# Hatch2020Trophy0805_1.net
KiCad netlist of a schematic drawn in EAGLE
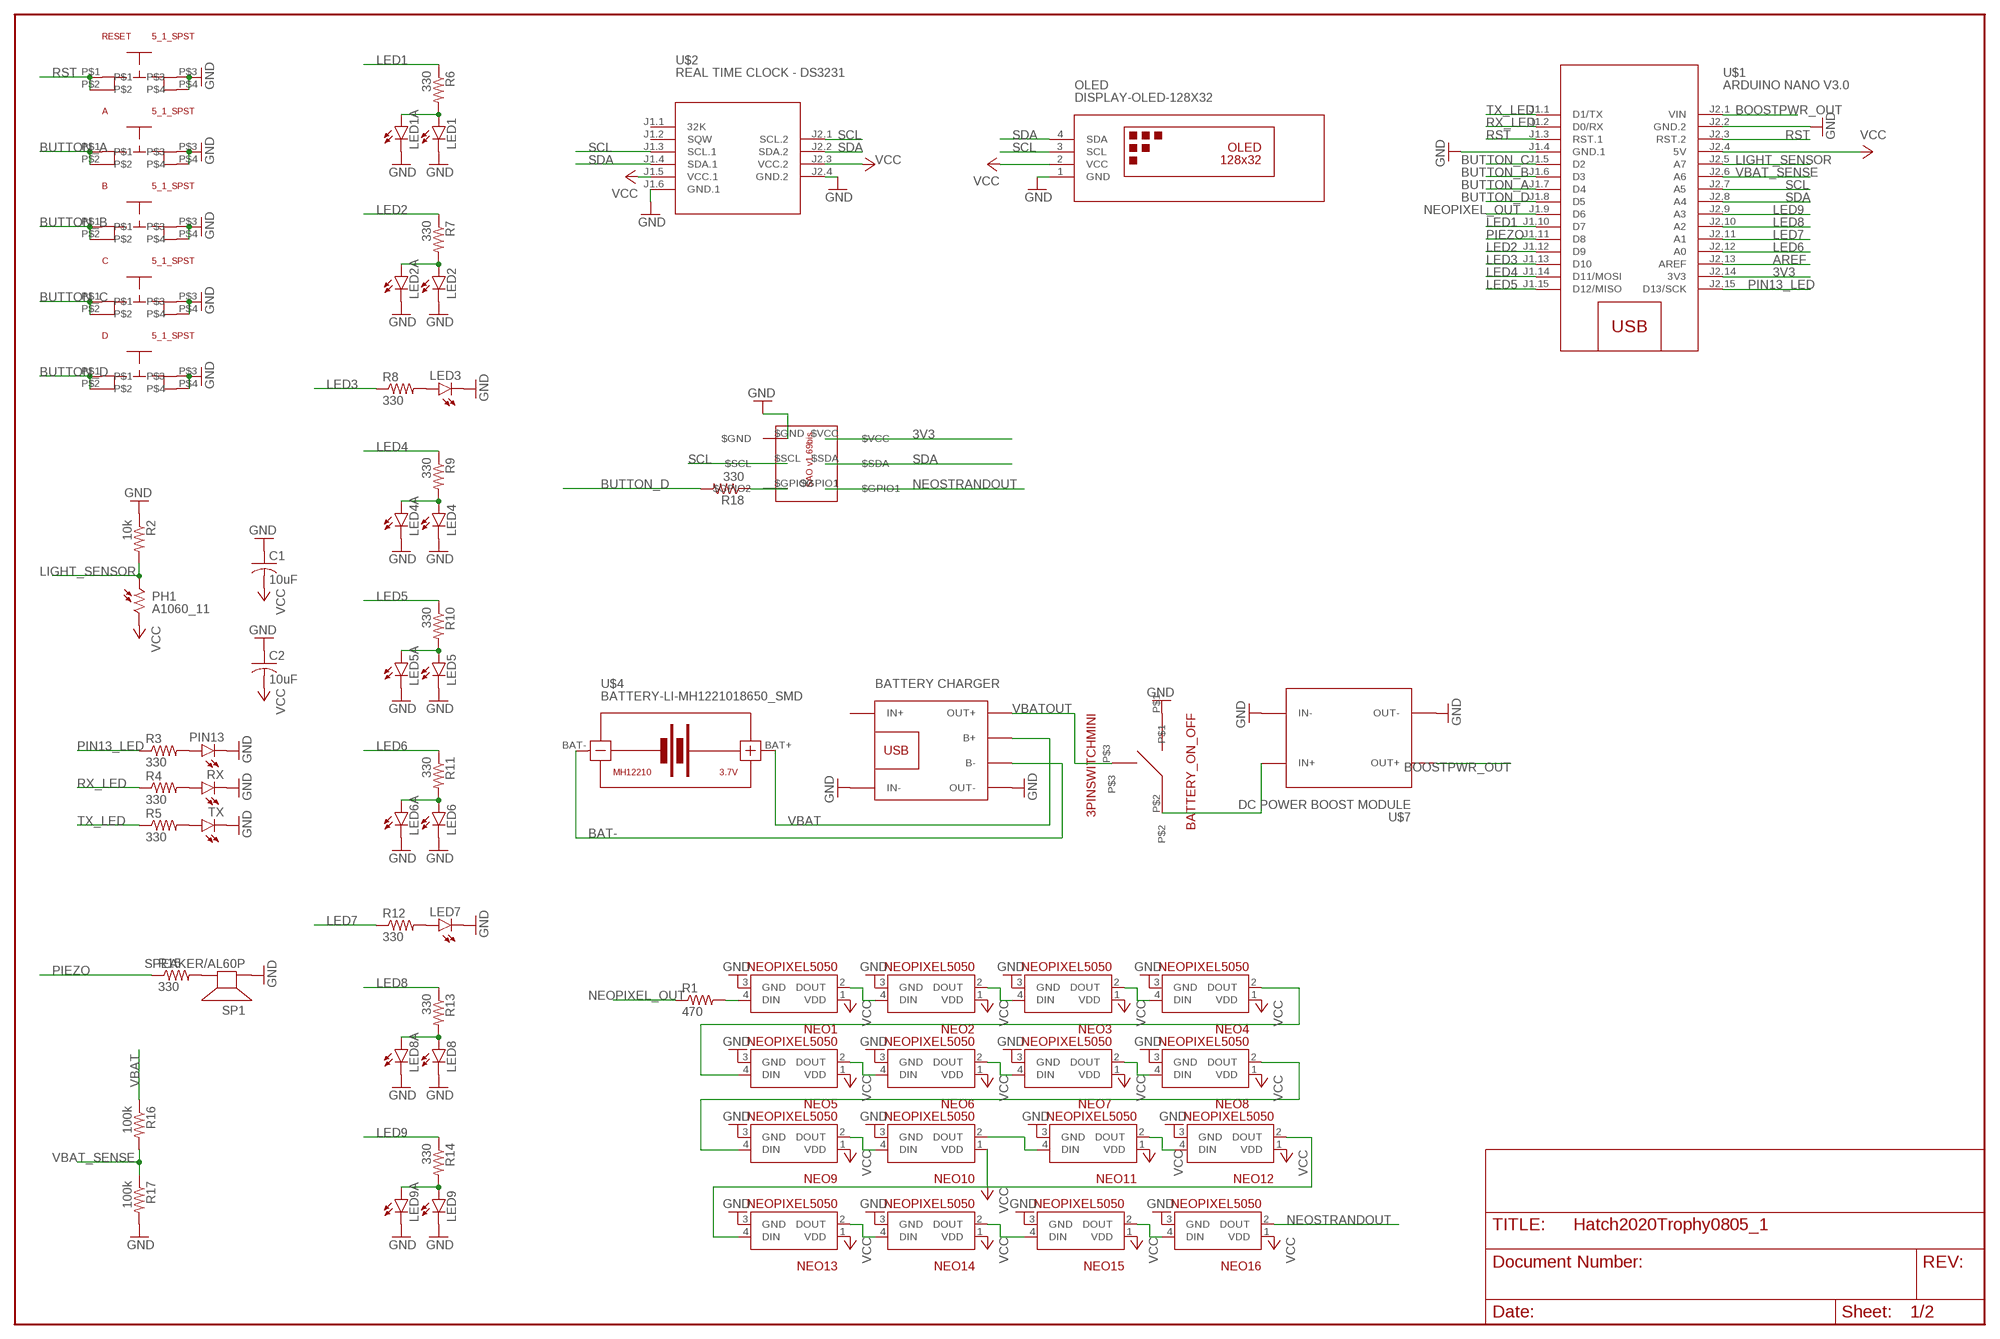
[diagram p0: schematic, sheet 1]

(export (version "E")
  (design (tool "Eeschema 10.0.6"))
  (components
    (comp (ref "A")
      (value "5_1_SPST")
      (footprint "eagle-import:5_1_SPST")
      (libsource (lib "eagle-import") (part "5_1_SPST"))
    )
    (comp (ref "B")
      (value "5_1_SPST")
      (footprint "eagle-import:5_1_SPST")
      (libsource (lib "eagle-import") (part "5_1_SPST"))
    )
    (comp (ref "BATTERY_ON_OFF")
      (value "3PINSWITCHMINI")
      (footprint "eagle-import:3PINMINI")
      (libsource (lib "eagle-import") (part "3PINSWITCHMINI"))
    )
    (comp (ref "C")
      (value "5_1_SPST")
      (footprint "eagle-import:5_1_SPST")
      (libsource (lib "eagle-import") (part "5_1_SPST"))
    )
    (comp (ref "C1")
      (value "10uF")
      (footprint "eagle-import:C0805")
      (libsource (lib "eagle-import") (part "C-USC0805"))
    )
    (comp (ref "C2")
      (value "10uF")
      (footprint "eagle-import:C0805")
      (libsource (lib "eagle-import") (part "C-USC0805"))
    )
    (comp (ref "D")
      (value "5_1_SPST")
      (footprint "eagle-import:5_1_SPST")
      (libsource (lib "eagle-import") (part "5_1_SPST"))
    )
    (comp (ref "LED1")
      (value "LEDSML0805")
      (footprint "eagle-import:SML0805")
      (libsource (lib "eagle-import") (part "LEDSML0805"))
    )
    (comp (ref "LED1A")
      (value "LEDSML0805")
      (footprint "eagle-import:SML0805")
      (libsource (lib "eagle-import") (part "LEDSML0805"))
    )
    (comp (ref "LED2")
      (value "LEDSML0805")
      (footprint "eagle-import:SML0805")
      (libsource (lib "eagle-import") (part "LEDSML0805"))
    )
    (comp (ref "LED2A")
      (value "LEDSML0805")
      (footprint "eagle-import:SML0805")
      (libsource (lib "eagle-import") (part "LEDSML0805"))
    )
    (comp (ref "LED3")
      (value "LEDSML0805")
      (footprint "eagle-import:SML0805")
      (libsource (lib "eagle-import") (part "LEDSML0805"))
    )
    (comp (ref "LED4")
      (value "LEDSML0805")
      (footprint "eagle-import:SML0805")
      (libsource (lib "eagle-import") (part "LEDSML0805"))
    )
    (comp (ref "LED4A")
      (value "LEDSML0805")
      (footprint "eagle-import:SML0805")
      (libsource (lib "eagle-import") (part "LEDSML0805"))
    )
    (comp (ref "LED5")
      (value "LEDSML0805")
      (footprint "eagle-import:SML0805")
      (libsource (lib "eagle-import") (part "LEDSML0805"))
    )
    (comp (ref "LED5A")
      (value "LEDSML0805")
      (footprint "eagle-import:SML0805")
      (libsource (lib "eagle-import") (part "LEDSML0805"))
    )
    (comp (ref "LED6")
      (value "LEDSML0805")
      (footprint "eagle-import:SML0805")
      (libsource (lib "eagle-import") (part "LEDSML0805"))
    )
    (comp (ref "LED6A")
      (value "LEDSML0805")
      (footprint "eagle-import:SML0805")
      (libsource (lib "eagle-import") (part "LEDSML0805"))
    )
    (comp (ref "LED7")
      (value "LEDSML0805")
      (footprint "eagle-import:SML0805")
      (libsource (lib "eagle-import") (part "LEDSML0805"))
    )
    (comp (ref "LED8")
      (value "LEDSML0805")
      (footprint "eagle-import:SML0805")
      (libsource (lib "eagle-import") (part "LEDSML0805"))
    )
    (comp (ref "LED8A")
      (value "LEDSML0805")
      (footprint "eagle-import:SML0805")
      (libsource (lib "eagle-import") (part "LEDSML0805"))
    )
    (comp (ref "LED9")
      (value "LEDSML0805")
      (footprint "eagle-import:SML0805")
      (libsource (lib "eagle-import") (part "LEDSML0805"))
    )
    (comp (ref "LED9A")
      (value "LEDSML0805")
      (footprint "eagle-import:SML0805")
      (libsource (lib "eagle-import") (part "LEDSML0805"))
    )
    (comp (ref "NEO1")
      (value "NEOPIXEL5050")
      (footprint "eagle-import:NEOPIXEL5050")
      (libsource (lib "eagle-import") (part "NEOPIXEL5050"))
    )
    (comp (ref "NEO2")
      (value "NEOPIXEL5050")
      (footprint "eagle-import:NEOPIXEL5050")
      (libsource (lib "eagle-import") (part "NEOPIXEL5050"))
    )
    (comp (ref "NEO3")
      (value "NEOPIXEL5050")
      (footprint "eagle-import:NEOPIXEL5050")
      (libsource (lib "eagle-import") (part "NEOPIXEL5050"))
    )
    (comp (ref "NEO4")
      (value "NEOPIXEL5050")
      (footprint "eagle-import:NEOPIXEL5050")
      (libsource (lib "eagle-import") (part "NEOPIXEL5050"))
    )
    (comp (ref "NEO5")
      (value "NEOPIXEL5050")
      (footprint "eagle-import:NEOPIXEL5050")
      (libsource (lib "eagle-import") (part "NEOPIXEL5050"))
    )
    (comp (ref "NEO6")
      (value "NEOPIXEL5050")
      (footprint "eagle-import:NEOPIXEL5050")
      (libsource (lib "eagle-import") (part "NEOPIXEL5050"))
    )
    (comp (ref "NEO7")
      (value "NEOPIXEL5050")
      (footprint "eagle-import:NEOPIXEL5050")
      (libsource (lib "eagle-import") (part "NEOPIXEL5050"))
    )
    (comp (ref "NEO8")
      (value "NEOPIXEL5050")
      (footprint "eagle-import:NEOPIXEL5050")
      (libsource (lib "eagle-import") (part "NEOPIXEL5050"))
    )
    (comp (ref "NEO9")
      (value "NEOPIXEL5050")
      (footprint "eagle-import:NEOPIXEL5050")
      (libsource (lib "eagle-import") (part "NEOPIXEL5050"))
    )
    (comp (ref "NEO10")
      (value "NEOPIXEL5050")
      (footprint "eagle-import:NEOPIXEL5050")
      (libsource (lib "eagle-import") (part "NEOPIXEL5050"))
    )
    (comp (ref "NEO11")
      (value "NEOPIXEL5050")
      (footprint "eagle-import:NEOPIXEL5050")
      (libsource (lib "eagle-import") (part "NEOPIXEL5050"))
    )
    (comp (ref "NEO12")
      (value "NEOPIXEL5050")
      (footprint "eagle-import:NEOPIXEL5050")
      (libsource (lib "eagle-import") (part "NEOPIXEL5050"))
    )
    (comp (ref "NEO13")
      (value "NEOPIXEL5050")
      (footprint "eagle-import:NEOPIXEL5050")
      (libsource (lib "eagle-import") (part "NEOPIXEL5050"))
    )
    (comp (ref "NEO14")
      (value "NEOPIXEL5050")
      (footprint "eagle-import:NEOPIXEL5050")
      (libsource (lib "eagle-import") (part "NEOPIXEL5050"))
    )
    (comp (ref "NEO15")
      (value "NEOPIXEL5050")
      (footprint "eagle-import:NEOPIXEL5050")
      (libsource (lib "eagle-import") (part "NEOPIXEL5050"))
    )
    (comp (ref "NEO16")
      (value "NEOPIXEL5050")
      (footprint "eagle-import:NEOPIXEL5050")
      (libsource (lib "eagle-import") (part "NEOPIXEL5050"))
    )
    (comp (ref "OLED")
      (value "DISPLAY-OLED-128X32")
      (footprint "eagle-import:DISPLAY-OLED-128X32")
      (libsource (lib "eagle-import") (part "DISPLAY-OLED-128X32"))
    )
    (comp (ref "PH1")
      (value "A1060_11")
      (footprint "eagle-import:T0-46-A10XX")
      (libsource (lib "eagle-import") (part "A1060_11"))
    )
    (comp (ref "PIN13")
      (value "LEDSML0805")
      (footprint "eagle-import:SML0805")
      (libsource (lib "eagle-import") (part "LEDSML0805"))
    )
    (comp (ref "R1")
      (value "470")
      (footprint "eagle-import:R0805")
      (libsource (lib "eagle-import") (part "R-US_R0805"))
    )
    (comp (ref "R2")
      (value "10k")
      (footprint "eagle-import:R0805")
      (libsource (lib "eagle-import") (part "R-US_R0805"))
    )
    (comp (ref "R3")
      (value "330")
      (footprint "eagle-import:R0805")
      (libsource (lib "eagle-import") (part "R-US_R0805"))
    )
    (comp (ref "R4")
      (value "330")
      (footprint "eagle-import:R0805")
      (libsource (lib "eagle-import") (part "R-US_R0805"))
    )
    (comp (ref "R5")
      (value "330")
      (footprint "eagle-import:R0805")
      (libsource (lib "eagle-import") (part "R-US_R0805"))
    )
    (comp (ref "R6")
      (value "330")
      (footprint "eagle-import:R0805")
      (libsource (lib "eagle-import") (part "R-US_R0805"))
    )
    (comp (ref "R7")
      (value "330")
      (footprint "eagle-import:R0805")
      (libsource (lib "eagle-import") (part "R-US_R0805"))
    )
    (comp (ref "R8")
      (value "330")
      (footprint "eagle-import:R0805")
      (libsource (lib "eagle-import") (part "R-US_R0805"))
    )
    (comp (ref "R9")
      (value "330")
      (footprint "eagle-import:R0805")
      (libsource (lib "eagle-import") (part "R-US_R0805"))
    )
    (comp (ref "R10")
      (value "330")
      (footprint "eagle-import:R0805")
      (libsource (lib "eagle-import") (part "R-US_R0805"))
    )
    (comp (ref "R11")
      (value "330")
      (footprint "eagle-import:R0805")
      (libsource (lib "eagle-import") (part "R-US_R0805"))
    )
    (comp (ref "R12")
      (value "330")
      (footprint "eagle-import:R0805")
      (libsource (lib "eagle-import") (part "R-US_R0805"))
    )
    (comp (ref "R13")
      (value "330")
      (footprint "eagle-import:R0805")
      (libsource (lib "eagle-import") (part "R-US_R0805"))
    )
    (comp (ref "R14")
      (value "330")
      (footprint "eagle-import:R0805")
      (libsource (lib "eagle-import") (part "R-US_R0805"))
    )
    (comp (ref "R15")
      (value "330")
      (footprint "eagle-import:R0805")
      (libsource (lib "eagle-import") (part "R-US_R0805"))
    )
    (comp (ref "R16")
      (value "100k")
      (footprint "eagle-import:R0805")
      (libsource (lib "eagle-import") (part "R-US_R0805"))
    )
    (comp (ref "R17")
      (value "100k")
      (footprint "eagle-import:R0805")
      (libsource (lib "eagle-import") (part "R-US_R0805"))
    )
    (comp (ref "R18")
      (value "330")
      (footprint "eagle-import:R1206")
      (libsource (lib "eagle-import") (part "R-US_R1206"))
    )
    (comp (ref "RESET")
      (value "5_1_SPST")
      (footprint "eagle-import:5_1_SPST")
      (libsource (lib "eagle-import") (part "5_1_SPST"))
    )
    (comp (ref "RX")
      (value "LEDSML0805")
      (footprint "eagle-import:SML0805")
      (libsource (lib "eagle-import") (part "LEDSML0805"))
    )
    (comp (ref "SP1")
      (value "SPEAKER/AL60P")
      (footprint "eagle-import:AL60P")
      (libsource (lib "eagle-import") (part "SPEAKER/AL60P"))
    )
    (comp (ref "TX")
      (value "LEDSML0805")
      (footprint "eagle-import:SML0805")
      (libsource (lib "eagle-import") (part "LEDSML0805"))
    )
    (comp (ref "U$1")
      (value "ARDUINO NANO V3.0")
      (footprint "eagle-import:ARDUINO-NANO-3.0")
      (libsource (lib "eagle-import") (part "ARDUINO-NANO-3.0"))
    )
    (comp (ref "U$2")
      (value "REAL TIME CLOCK - DS3231")
      (footprint "eagle-import:RTC-DS3231-AT24C32")
      (libsource (lib "eagle-import") (part "RTC-DS3231-AT24C32"))
    )
    (comp (ref "U$3")
      (value "SAO-1.69")
      (footprint "eagle-import:2X3-SHROUDED-FEMALE")
      (libsource (lib "eagle-import") (part "SAO-1.69"))
    )
    (comp (ref "U$4")
      (value "BATTERY-LI-MH1221018650_SMD")
      (footprint "eagle-import:BATTERY_18650_SMD")
      (libsource (lib "eagle-import") (part "BATTERY-LI-MH1221018650_SMD"))
    )
    (comp (ref "U$6")
      (value "BATTERY CHARGER")
      (footprint "eagle-import:BAT_CHARGE_LOW_FP")
      (libsource (lib "eagle-import") (part "BATTERY-CHARGER-LI-PROTLOW_FP"))
    )
    (comp (ref "U$7")
      (value "DC POWER BOOST MODULE")
      (footprint "eagle-import:DC-DC-STEP-UP-LOW_FP")
      (libsource (lib "eagle-import") (part "DC-DC-STEP-UP-MT3608LOW_FP"))
    )
  )
  (nets
    (net (code "1") (name "3V3") (class "Default")
      (node (ref "U$1") (pin "J2.14") (pinfunction "3V3_J2.14") (pintype "power_in"))
      (node (ref "U$3") (pin "$VCC") (pinfunction "$VCC_$VCC") (pintype "bidirectional"))
    )
    (net (code "2") (name "AREF") (class "Default")
      (node (ref "U$1") (pin "J2.13") (pinfunction "AREF_J2.13") (pintype "bidirectional"))
    )
    (net (code "3") (name "BAT-") (class "Default")
      (node (ref "U$4") (pin "BAT-") (pinfunction "BAT-_BAT-") (pintype "power_in"))
      (node (ref "U$6") (pin "B-") (pinfunction "B-_B-") (pintype "bidirectional"))
    )
    (net (code "4") (name "BOOSTPWR_OUT") (class "Default")
      (node (ref "U$1") (pin "J2.1") (pinfunction "VIN_J2.1") (pintype "power_in"))
      (node (ref "U$7") (pin "OUT+") (pinfunction "OUT+_OUT+") (pintype "bidirectional"))
    )
    (net (code "5") (name "BUTTON_A") (class "Default")
      (node (ref "A") (pin "P$1") (pinfunction "P$1_P$1") (pintype "bidirectional"))
      (node (ref "A") (pin "P$2") (pinfunction "P$2_P$2") (pintype "bidirectional"))
      (node (ref "U$1") (pin "J1.7") (pinfunction "D4_J1.7") (pintype "bidirectional"))
    )
    (net (code "6") (name "BUTTON_B") (class "Default")
      (node (ref "B") (pin "P$1") (pinfunction "P$1_P$1") (pintype "bidirectional"))
      (node (ref "B") (pin "P$2") (pinfunction "P$2_P$2") (pintype "bidirectional"))
      (node (ref "U$1") (pin "J1.6") (pinfunction "D3_J1.6") (pintype "bidirectional"))
    )
    (net (code "7") (name "BUTTON_C") (class "Default")
      (node (ref "C") (pin "P$1") (pinfunction "P$1_P$1") (pintype "bidirectional"))
      (node (ref "C") (pin "P$2") (pinfunction "P$2_P$2") (pintype "bidirectional"))
      (node (ref "U$1") (pin "J1.5") (pinfunction "D2_J1.5") (pintype "bidirectional"))
    )
    (net (code "8") (name "BUTTON_D") (class "Default")
      (node (ref "D") (pin "P$1") (pinfunction "P$1_P$1") (pintype "bidirectional"))
      (node (ref "D") (pin "P$2") (pinfunction "P$2_P$2") (pintype "bidirectional"))
      (node (ref "R18") (pin "2") (pinfunction "2_2") (pintype "passive"))
      (node (ref "U$1") (pin "J1.8") (pinfunction "D5_J1.8") (pintype "bidirectional"))
    )
    (net (code "9") (name "GND") (class "Default")
      (node (ref "A") (pin "P$3") (pinfunction "P$3_P$3") (pintype "bidirectional"))
      (node (ref "A") (pin "P$4") (pinfunction "P$4_P$4") (pintype "bidirectional"))
      (node (ref "B") (pin "P$3") (pinfunction "P$3_P$3") (pintype "bidirectional"))
      (node (ref "B") (pin "P$4") (pinfunction "P$4_P$4") (pintype "bidirectional"))
      (node (ref "BATTERY_ON_OFF") (pin "P$1") (pinfunction "P$1_P$1") (pintype "bidirectional"))
      (node (ref "C") (pin "P$3") (pinfunction "P$3_P$3") (pintype "bidirectional"))
      (node (ref "C") (pin "P$4") (pinfunction "P$4_P$4") (pintype "bidirectional"))
      (node (ref "C1") (pin "1") (pinfunction "1_1") (pintype "passive"))
      (node (ref "C2") (pin "1") (pinfunction "1_1") (pintype "passive"))
      (node (ref "D") (pin "P$3") (pinfunction "P$3_P$3") (pintype "bidirectional"))
      (node (ref "D") (pin "P$4") (pinfunction "P$4_P$4") (pintype "bidirectional"))
      (node (ref "LED1") (pin "C") (pinfunction "C_C") (pintype "passive"))
      (node (ref "LED1A") (pin "C") (pinfunction "C_C") (pintype "passive"))
      (node (ref "LED2") (pin "C") (pinfunction "C_C") (pintype "passive"))
      (node (ref "LED2A") (pin "C") (pinfunction "C_C") (pintype "passive"))
      (node (ref "LED3") (pin "C") (pinfunction "C_C") (pintype "passive"))
      (node (ref "LED4") (pin "C") (pinfunction "C_C") (pintype "passive"))
      (node (ref "LED4A") (pin "C") (pinfunction "C_C") (pintype "passive"))
      (node (ref "LED5") (pin "C") (pinfunction "C_C") (pintype "passive"))
      (node (ref "LED5A") (pin "C") (pinfunction "C_C") (pintype "passive"))
      (node (ref "LED6") (pin "C") (pinfunction "C_C") (pintype "passive"))
      (node (ref "LED6A") (pin "C") (pinfunction "C_C") (pintype "passive"))
      (node (ref "LED7") (pin "C") (pinfunction "C_C") (pintype "passive"))
      (node (ref "LED8") (pin "C") (pinfunction "C_C") (pintype "passive"))
      (node (ref "LED8A") (pin "C") (pinfunction "C_C") (pintype "passive"))
      (node (ref "LED9") (pin "C") (pinfunction "C_C") (pintype "passive"))
      (node (ref "LED9A") (pin "C") (pinfunction "C_C") (pintype "passive"))
      (node (ref "NEO1") (pin "3") (pinfunction "GND_3") (pintype "bidirectional"))
      (node (ref "NEO10") (pin "3") (pinfunction "GND_3") (pintype "bidirectional"))
      (node (ref "NEO11") (pin "3") (pinfunction "GND_3") (pintype "bidirectional"))
      (node (ref "NEO12") (pin "3") (pinfunction "GND_3") (pintype "bidirectional"))
      (node (ref "NEO13") (pin "3") (pinfunction "GND_3") (pintype "bidirectional"))
      (node (ref "NEO14") (pin "3") (pinfunction "GND_3") (pintype "bidirectional"))
      (node (ref "NEO15") (pin "3") (pinfunction "GND_3") (pintype "bidirectional"))
      (node (ref "NEO16") (pin "3") (pinfunction "GND_3") (pintype "bidirectional"))
      (node (ref "NEO2") (pin "3") (pinfunction "GND_3") (pintype "bidirectional"))
      (node (ref "NEO3") (pin "3") (pinfunction "GND_3") (pintype "bidirectional"))
      (node (ref "NEO4") (pin "3") (pinfunction "GND_3") (pintype "bidirectional"))
      (node (ref "NEO5") (pin "3") (pinfunction "GND_3") (pintype "bidirectional"))
      (node (ref "NEO6") (pin "3") (pinfunction "GND_3") (pintype "bidirectional"))
      (node (ref "NEO7") (pin "3") (pinfunction "GND_3") (pintype "bidirectional"))
      (node (ref "NEO8") (pin "3") (pinfunction "GND_3") (pintype "bidirectional"))
      (node (ref "NEO9") (pin "3") (pinfunction "GND_3") (pintype "bidirectional"))
      (node (ref "OLED") (pin "1") (pinfunction "GND_1") (pintype "power_in"))
      (node (ref "PIN13") (pin "C") (pinfunction "C_C") (pintype "passive"))
      (node (ref "R17") (pin "2") (pinfunction "2_2") (pintype "passive"))
      (node (ref "R2") (pin "1") (pinfunction "1_1") (pintype "passive"))
      (node (ref "RESET") (pin "P$3") (pinfunction "P$3_P$3") (pintype "bidirectional"))
      (node (ref "RESET") (pin "P$4") (pinfunction "P$4_P$4") (pintype "bidirectional"))
      (node (ref "RX") (pin "C") (pinfunction "C_C") (pintype "passive"))
      (node (ref "SP1") (pin "1") (pinfunction "+_1") (pintype "passive"))
      (node (ref "TX") (pin "C") (pinfunction "C_C") (pintype "passive"))
      (node (ref "U$1") (pin "J1.4") (pinfunction "GND.1_J1.4") (pintype "power_in"))
      (node (ref "U$1") (pin "J2.2") (pinfunction "GND.2_J2.2") (pintype "power_in"))
      (node (ref "U$2") (pin "J1.6") (pinfunction "GND.1_J1.6") (pintype "power_in"))
      (node (ref "U$2") (pin "J2.4") (pinfunction "GND.2_J2.4") (pintype "power_in"))
      (node (ref "U$3") (pin "$GND") (pinfunction "$GND_$GND") (pintype "bidirectional"))
      (node (ref "U$6") (pin "IN-") (pinfunction "IN-_IN-") (pintype "bidirectional"))
      (node (ref "U$6") (pin "OUT-") (pinfunction "OUT-_OUT-") (pintype "bidirectional"))
      (node (ref "U$7") (pin "IN-") (pinfunction "IN-_IN-") (pintype "bidirectional"))
      (node (ref "U$7") (pin "OUT-") (pinfunction "OUT-_OUT-") (pintype "bidirectional"))
    )
    (net (code "10") (name "LED1") (class "Default")
      (node (ref "R6") (pin "1") (pinfunction "1_1") (pintype "passive"))
      (node (ref "U$1") (pin "J1.10") (pinfunction "D7_J1.10") (pintype "bidirectional"))
    )
    (net (code "11") (name "LED2") (class "Default")
      (node (ref "R7") (pin "1") (pinfunction "1_1") (pintype "passive"))
      (node (ref "U$1") (pin "J1.12") (pinfunction "D9_J1.12") (pintype "bidirectional"))
    )
    (net (code "12") (name "LED3") (class "Default")
      (node (ref "R8") (pin "1") (pinfunction "1_1") (pintype "passive"))
      (node (ref "U$1") (pin "J1.13") (pinfunction "D10_J1.13") (pintype "bidirectional"))
    )
    (net (code "13") (name "LED4") (class "Default")
      (node (ref "R9") (pin "1") (pinfunction "1_1") (pintype "passive"))
      (node (ref "U$1") (pin "J1.14") (pinfunction "D11/MOSI_J1.14") (pintype "bidirectional"))
    )
    (net (code "14") (name "LED5") (class "Default")
      (node (ref "R10") (pin "1") (pinfunction "1_1") (pintype "passive"))
      (node (ref "U$1") (pin "J1.15") (pinfunction "D12/MISO_J1.15") (pintype "bidirectional"))
    )
    (net (code "15") (name "LED6") (class "Default")
      (node (ref "R11") (pin "1") (pinfunction "1_1") (pintype "passive"))
      (node (ref "U$1") (pin "J2.12") (pinfunction "A0_J2.12") (pintype "bidirectional"))
    )
    (net (code "16") (name "LED7") (class "Default")
      (node (ref "R12") (pin "1") (pinfunction "1_1") (pintype "passive"))
      (node (ref "U$1") (pin "J2.11") (pinfunction "A1_J2.11") (pintype "bidirectional"))
    )
    (net (code "17") (name "LED8") (class "Default")
      (node (ref "R13") (pin "1") (pinfunction "1_1") (pintype "passive"))
      (node (ref "U$1") (pin "J2.10") (pinfunction "A2_J2.10") (pintype "bidirectional"))
    )
    (net (code "18") (name "LED9") (class "Default")
      (node (ref "R14") (pin "1") (pinfunction "1_1") (pintype "passive"))
      (node (ref "U$1") (pin "J2.9") (pinfunction "A3_J2.9") (pintype "bidirectional"))
    )
    (net (code "19") (name "LIGHT_SENSOR") (class "Default")
      (node (ref "PH1") (pin "1") (pinfunction "1_1") (pintype "passive"))
      (node (ref "R2") (pin "2") (pinfunction "2_2") (pintype "passive"))
      (node (ref "U$1") (pin "J2.5") (pinfunction "A7_J2.5") (pintype "bidirectional"))
    )
    (net (code "20") (name "NEOPIXEL_OUT") (class "Default")
      (node (ref "R1") (pin "1") (pinfunction "1_1") (pintype "passive"))
      (node (ref "U$1") (pin "J1.9") (pinfunction "D6_J1.9") (pintype "bidirectional"))
    )
    (net (code "21") (name "NEOSTRANDOUT") (class "Default")
      (node (ref "NEO16") (pin "2") (pinfunction "DOUT_2") (pintype "bidirectional"))
      (node (ref "U$3") (pin "$GPIO1") (pinfunction "$GPIO1_$GPIO1") (pintype "bidirectional"))
    )
    (net (code "22") (name "Net-(BATTERY_ON_OFF-PadP$2)") (class "Default")
      (node (ref "BATTERY_ON_OFF") (pin "P$2") (pinfunction "P$2_P$2") (pintype "bidirectional"))
      (node (ref "U$7") (pin "IN+") (pinfunction "IN+_IN+") (pintype "bidirectional"))
    )
    (net (code "23") (name "Net-(LED1-PadA)") (class "Default")
      (node (ref "LED1") (pin "A") (pinfunction "A_A") (pintype "passive"))
      (node (ref "LED1A") (pin "A") (pinfunction "A_A") (pintype "passive"))
      (node (ref "R6") (pin "2") (pinfunction "2_2") (pintype "passive"))
    )
    (net (code "24") (name "Net-(LED2-PadA)") (class "Default")
      (node (ref "LED2") (pin "A") (pinfunction "A_A") (pintype "passive"))
      (node (ref "LED2A") (pin "A") (pinfunction "A_A") (pintype "passive"))
      (node (ref "R7") (pin "2") (pinfunction "2_2") (pintype "passive"))
    )
    (net (code "25") (name "Net-(LED3-PadA)") (class "Default")
      (node (ref "LED3") (pin "A") (pinfunction "A_A") (pintype "passive"))
      (node (ref "R8") (pin "2") (pinfunction "2_2") (pintype "passive"))
    )
    (net (code "26") (name "Net-(LED4-PadA)") (class "Default")
      (node (ref "LED4") (pin "A") (pinfunction "A_A") (pintype "passive"))
      (node (ref "LED4A") (pin "A") (pinfunction "A_A") (pintype "passive"))
      (node (ref "R9") (pin "2") (pinfunction "2_2") (pintype "passive"))
    )
    (net (code "27") (name "Net-(LED5-PadA)") (class "Default")
      (node (ref "LED5") (pin "A") (pinfunction "A_A") (pintype "passive"))
      (node (ref "LED5A") (pin "A") (pinfunction "A_A") (pintype "passive"))
      (node (ref "R10") (pin "2") (pinfunction "2_2") (pintype "passive"))
    )
    (net (code "28") (name "Net-(LED6-PadA)") (class "Default")
      (node (ref "LED6") (pin "A") (pinfunction "A_A") (pintype "passive"))
      (node (ref "LED6A") (pin "A") (pinfunction "A_A") (pintype "passive"))
      (node (ref "R11") (pin "2") (pinfunction "2_2") (pintype "passive"))
    )
    (net (code "29") (name "Net-(LED7-PadA)") (class "Default")
      (node (ref "LED7") (pin "A") (pinfunction "A_A") (pintype "passive"))
      (node (ref "R12") (pin "2") (pinfunction "2_2") (pintype "passive"))
    )
    (net (code "30") (name "Net-(LED8-PadA)") (class "Default")
      (node (ref "LED8") (pin "A") (pinfunction "A_A") (pintype "passive"))
      (node (ref "LED8A") (pin "A") (pinfunction "A_A") (pintype "passive"))
      (node (ref "R13") (pin "2") (pinfunction "2_2") (pintype "passive"))
    )
    (net (code "31") (name "Net-(LED9-PadA)") (class "Default")
      (node (ref "LED9") (pin "A") (pinfunction "A_A") (pintype "passive"))
      (node (ref "LED9A") (pin "A") (pinfunction "A_A") (pintype "passive"))
      (node (ref "R14") (pin "2") (pinfunction "2_2") (pintype "passive"))
    )
    (net (code "32") (name "Net-(NEO1-DIN)") (class "Default")
      (node (ref "NEO1") (pin "4") (pinfunction "DIN_4") (pintype "bidirectional"))
      (node (ref "R1") (pin "2") (pinfunction "2_2") (pintype "passive"))
    )
    (net (code "33") (name "Net-(NEO1-DOUT)") (class "Default")
      (node (ref "NEO1") (pin "2") (pinfunction "DOUT_2") (pintype "bidirectional"))
      (node (ref "NEO2") (pin "4") (pinfunction "DIN_4") (pintype "bidirectional"))
    )
    (net (code "34") (name "Net-(NEO2-DOUT)") (class "Default")
      (node (ref "NEO2") (pin "2") (pinfunction "DOUT_2") (pintype "bidirectional"))
      (node (ref "NEO3") (pin "4") (pinfunction "DIN_4") (pintype "bidirectional"))
    )
    (net (code "35") (name "Net-(NEO3-DOUT)") (class "Default")
      (node (ref "NEO3") (pin "2") (pinfunction "DOUT_2") (pintype "bidirectional"))
      (node (ref "NEO4") (pin "4") (pinfunction "DIN_4") (pintype "bidirectional"))
    )
    (net (code "36") (name "Net-(NEO4-DOUT)") (class "Default")
      (node (ref "NEO4") (pin "2") (pinfunction "DOUT_2") (pintype "bidirectional"))
      (node (ref "NEO5") (pin "4") (pinfunction "DIN_4") (pintype "bidirectional"))
    )
    (net (code "37") (name "Net-(NEO5-DOUT)") (class "Default")
      (node (ref "NEO5") (pin "2") (pinfunction "DOUT_2") (pintype "bidirectional"))
      (node (ref "NEO6") (pin "4") (pinfunction "DIN_4") (pintype "bidirectional"))
    )
    (net (code "38") (name "Net-(NEO6-DOUT)") (class "Default")
      (node (ref "NEO6") (pin "2") (pinfunction "DOUT_2") (pintype "bidirectional"))
      (node (ref "NEO7") (pin "4") (pinfunction "DIN_4") (pintype "bidirectional"))
    )
    (net (code "39") (name "Net-(NEO7-DOUT)") (class "Default")
      (node (ref "NEO7") (pin "2") (pinfunction "DOUT_2") (pintype "bidirectional"))
      (node (ref "NEO8") (pin "4") (pinfunction "DIN_4") (pintype "bidirectional"))
    )
    (net (code "40") (name "Net-(NEO8-DOUT)") (class "Default")
      (node (ref "NEO8") (pin "2") (pinfunction "DOUT_2") (pintype "bidirectional"))
      (node (ref "NEO9") (pin "4") (pinfunction "DIN_4") (pintype "bidirectional"))
    )
    (net (code "41") (name "Net-(NEO10-DIN)") (class "Default")
      (node (ref "NEO10") (pin "4") (pinfunction "DIN_4") (pintype "bidirectional"))
      (node (ref "NEO9") (pin "2") (pinfunction "DOUT_2") (pintype "bidirectional"))
    )
    (net (code "42") (name "Net-(NEO10-DOUT)") (class "Default")
      (node (ref "NEO10") (pin "2") (pinfunction "DOUT_2") (pintype "bidirectional"))
      (node (ref "NEO11") (pin "4") (pinfunction "DIN_4") (pintype "bidirectional"))
    )
    (net (code "43") (name "Net-(NEO11-DOUT)") (class "Default")
      (node (ref "NEO11") (pin "2") (pinfunction "DOUT_2") (pintype "bidirectional"))
      (node (ref "NEO12") (pin "4") (pinfunction "DIN_4") (pintype "bidirectional"))
    )
    (net (code "44") (name "Net-(NEO12-DOUT)") (class "Default")
      (node (ref "NEO12") (pin "2") (pinfunction "DOUT_2") (pintype "bidirectional"))
      (node (ref "NEO13") (pin "4") (pinfunction "DIN_4") (pintype "bidirectional"))
    )
    (net (code "45") (name "Net-(NEO13-DOUT)") (class "Default")
      (node (ref "NEO13") (pin "2") (pinfunction "DOUT_2") (pintype "bidirectional"))
      (node (ref "NEO14") (pin "4") (pinfunction "DIN_4") (pintype "bidirectional"))
    )
    (net (code "46") (name "Net-(NEO14-DOUT)") (class "Default")
      (node (ref "NEO14") (pin "2") (pinfunction "DOUT_2") (pintype "bidirectional"))
      (node (ref "NEO15") (pin "4") (pinfunction "DIN_4") (pintype "bidirectional"))
    )
    (net (code "47") (name "Net-(NEO15-DOUT)") (class "Default")
      (node (ref "NEO15") (pin "2") (pinfunction "DOUT_2") (pintype "bidirectional"))
      (node (ref "NEO16") (pin "4") (pinfunction "DIN_4") (pintype "bidirectional"))
    )
    (net (code "48") (name "Net-(PIN13-PadA)") (class "Default")
      (node (ref "PIN13") (pin "A") (pinfunction "A_A") (pintype "passive"))
      (node (ref "R3") (pin "2") (pinfunction "2_2") (pintype "passive"))
    )
    (net (code "49") (name "Net-(R4-Pad2)") (class "Default")
      (node (ref "R4") (pin "2") (pinfunction "2_2") (pintype "passive"))
      (node (ref "RX") (pin "A") (pinfunction "A_A") (pintype "passive"))
    )
    (net (code "50") (name "Net-(R5-Pad2)") (class "Default")
      (node (ref "R5") (pin "2") (pinfunction "2_2") (pintype "passive"))
      (node (ref "TX") (pin "A") (pinfunction "A_A") (pintype "passive"))
    )
    (net (code "51") (name "Net-(R18-Pad1)") (class "Default")
      (node (ref "R18") (pin "1") (pinfunction "1_1") (pintype "passive"))
      (node (ref "U$3") (pin "$GPIO2") (pinfunction "$GPIO2_$GPIO2") (pintype "bidirectional"))
    )
    (net (code "52") (name "Net-(SP1--)") (class "Default")
      (node (ref "R15") (pin "2") (pinfunction "2_2") (pintype "passive"))
      (node (ref "SP1") (pin "2") (pinfunction "-_2") (pintype "passive"))
    )
    (net (code "53") (name "PIEZO") (class "Default")
      (node (ref "R15") (pin "1") (pinfunction "1_1") (pintype "passive"))
      (node (ref "U$1") (pin "J1.11") (pinfunction "D8_J1.11") (pintype "bidirectional"))
    )
    (net (code "54") (name "PIN13_LED") (class "Default")
      (node (ref "R3") (pin "1") (pinfunction "1_1") (pintype "passive"))
      (node (ref "U$1") (pin "J2.15") (pinfunction "D13/SCK_J2.15") (pintype "bidirectional"))
    )
    (net (code "55") (name "RST") (class "Default")
      (node (ref "RESET") (pin "P$1") (pinfunction "P$1_P$1") (pintype "bidirectional"))
      (node (ref "RESET") (pin "P$2") (pinfunction "P$2_P$2") (pintype "bidirectional"))
      (node (ref "U$1") (pin "J1.3") (pinfunction "RST.1_J1.3") (pintype "bidirectional"))
      (node (ref "U$1") (pin "J2.3") (pinfunction "RST.2_J2.3") (pintype "bidirectional"))
    )
    (net (code "56") (name "RX_LED") (class "Default")
      (node (ref "R4") (pin "1") (pinfunction "1_1") (pintype "passive"))
      (node (ref "U$1") (pin "J1.2") (pinfunction "D0/RX_J1.2") (pintype "bidirectional"))
    )
    (net (code "57") (name "SCL") (class "Default")
      (node (ref "OLED") (pin "3") (pinfunction "SCL_3") (pintype "bidirectional"))
      (node (ref "U$1") (pin "J2.7") (pinfunction "A5_J2.7") (pintype "bidirectional"))
      (node (ref "U$2") (pin "J1.3") (pinfunction "SCL.1_J1.3") (pintype "bidirectional"))
      (node (ref "U$2") (pin "J2.1") (pinfunction "SCL.2_J2.1") (pintype "bidirectional"))
      (node (ref "U$3") (pin "$SCL") (pinfunction "$SCL_$SCL") (pintype "bidirectional"))
    )
    (net (code "58") (name "SDA") (class "Default")
      (node (ref "OLED") (pin "4") (pinfunction "SDA_4") (pintype "bidirectional"))
      (node (ref "U$1") (pin "J2.8") (pinfunction "A4_J2.8") (pintype "bidirectional"))
      (node (ref "U$2") (pin "J1.4") (pinfunction "SDA.1_J1.4") (pintype "bidirectional"))
      (node (ref "U$2") (pin "J2.2") (pinfunction "SDA.2_J2.2") (pintype "bidirectional"))
      (node (ref "U$3") (pin "$SDA") (pinfunction "$SDA_$SDA") (pintype "bidirectional"))
    )
    (net (code "59") (name "TX_LED") (class "Default")
      (node (ref "R5") (pin "1") (pinfunction "1_1") (pintype "passive"))
      (node (ref "U$1") (pin "J1.1") (pinfunction "D1/TX_J1.1") (pintype "bidirectional"))
    )
    (net (code "60") (name "VBAT") (class "Default")
      (node (ref "R16") (pin "1") (pinfunction "1_1") (pintype "passive"))
      (node (ref "U$4") (pin "BAT+") (pinfunction "BAT+_BAT+") (pintype "power_in"))
      (node (ref "U$6") (pin "B+") (pinfunction "B+_B+") (pintype "bidirectional"))
    )
    (net (code "61") (name "VBATOUT") (class "Default")
      (node (ref "BATTERY_ON_OFF") (pin "P$3") (pinfunction "P$3_P$3") (pintype "bidirectional"))
      (node (ref "U$6") (pin "OUT+") (pinfunction "OUT+_OUT+") (pintype "bidirectional"))
    )
    (net (code "62") (name "VBAT_SENSE") (class "Default")
      (node (ref "R16") (pin "2") (pinfunction "2_2") (pintype "passive"))
      (node (ref "R17") (pin "1") (pinfunction "1_1") (pintype "passive"))
      (node (ref "U$1") (pin "J2.6") (pinfunction "A6_J2.6") (pintype "bidirectional"))
    )
    (net (code "63") (name "VCC") (class "Default")
      (node (ref "C1") (pin "2") (pinfunction "2_2") (pintype "passive"))
      (node (ref "C2") (pin "2") (pinfunction "2_2") (pintype "passive"))
      (node (ref "NEO1") (pin "1") (pinfunction "VDD_1") (pintype "bidirectional"))
      (node (ref "NEO10") (pin "1") (pinfunction "VDD_1") (pintype "bidirectional"))
      (node (ref "NEO11") (pin "1") (pinfunction "VDD_1") (pintype "bidirectional"))
      (node (ref "NEO12") (pin "1") (pinfunction "VDD_1") (pintype "bidirectional"))
      (node (ref "NEO13") (pin "1") (pinfunction "VDD_1") (pintype "bidirectional"))
      (node (ref "NEO14") (pin "1") (pinfunction "VDD_1") (pintype "bidirectional"))
      (node (ref "NEO15") (pin "1") (pinfunction "VDD_1") (pintype "bidirectional"))
      (node (ref "NEO16") (pin "1") (pinfunction "VDD_1") (pintype "bidirectional"))
      (node (ref "NEO2") (pin "1") (pinfunction "VDD_1") (pintype "bidirectional"))
      (node (ref "NEO3") (pin "1") (pinfunction "VDD_1") (pintype "bidirectional"))
      (node (ref "NEO4") (pin "1") (pinfunction "VDD_1") (pintype "bidirectional"))
      (node (ref "NEO5") (pin "1") (pinfunction "VDD_1") (pintype "bidirectional"))
      (node (ref "NEO6") (pin "1") (pinfunction "VDD_1") (pintype "bidirectional"))
      (node (ref "NEO7") (pin "1") (pinfunction "VDD_1") (pintype "bidirectional"))
      (node (ref "NEO8") (pin "1") (pinfunction "VDD_1") (pintype "bidirectional"))
      (node (ref "NEO9") (pin "1") (pinfunction "VDD_1") (pintype "bidirectional"))
      (node (ref "OLED") (pin "2") (pinfunction "VCC_2") (pintype "power_in"))
      (node (ref "PH1") (pin "2") (pinfunction "2_2") (pintype "passive"))
      (node (ref "U$1") (pin "J2.4") (pinfunction "5V_J2.4") (pintype "power_in"))
      (node (ref "U$2") (pin "J1.5") (pinfunction "VCC.1_J1.5") (pintype "power_in"))
      (node (ref "U$2") (pin "J2.3") (pinfunction "VCC.2_J2.3") (pintype "power_in"))
    )
    (net (code "64") (name "unconnected-(U$2-32K-PadJ1.1)") (class "Default")
      (node (ref "U$2") (pin "J1.1") (pinfunction "32K_J1.1") (pintype "bidirectional"))
    )
    (net (code "65") (name "unconnected-(U$2-SQW-PadJ1.2)") (class "Default")
      (node (ref "U$2") (pin "J1.2") (pinfunction "SQW_J1.2") (pintype "bidirectional"))
    )
    (net (code "66") (name "unconnected-(U$6-PadIN+)") (class "Default")
      (node (ref "U$6") (pin "IN+") (pinfunction "IN+_IN+") (pintype "bidirectional"))
    )
  )
)
